# OneWireGateway_2x_0_1.net
KiCad netlist of a schematic drawn in EAGLE
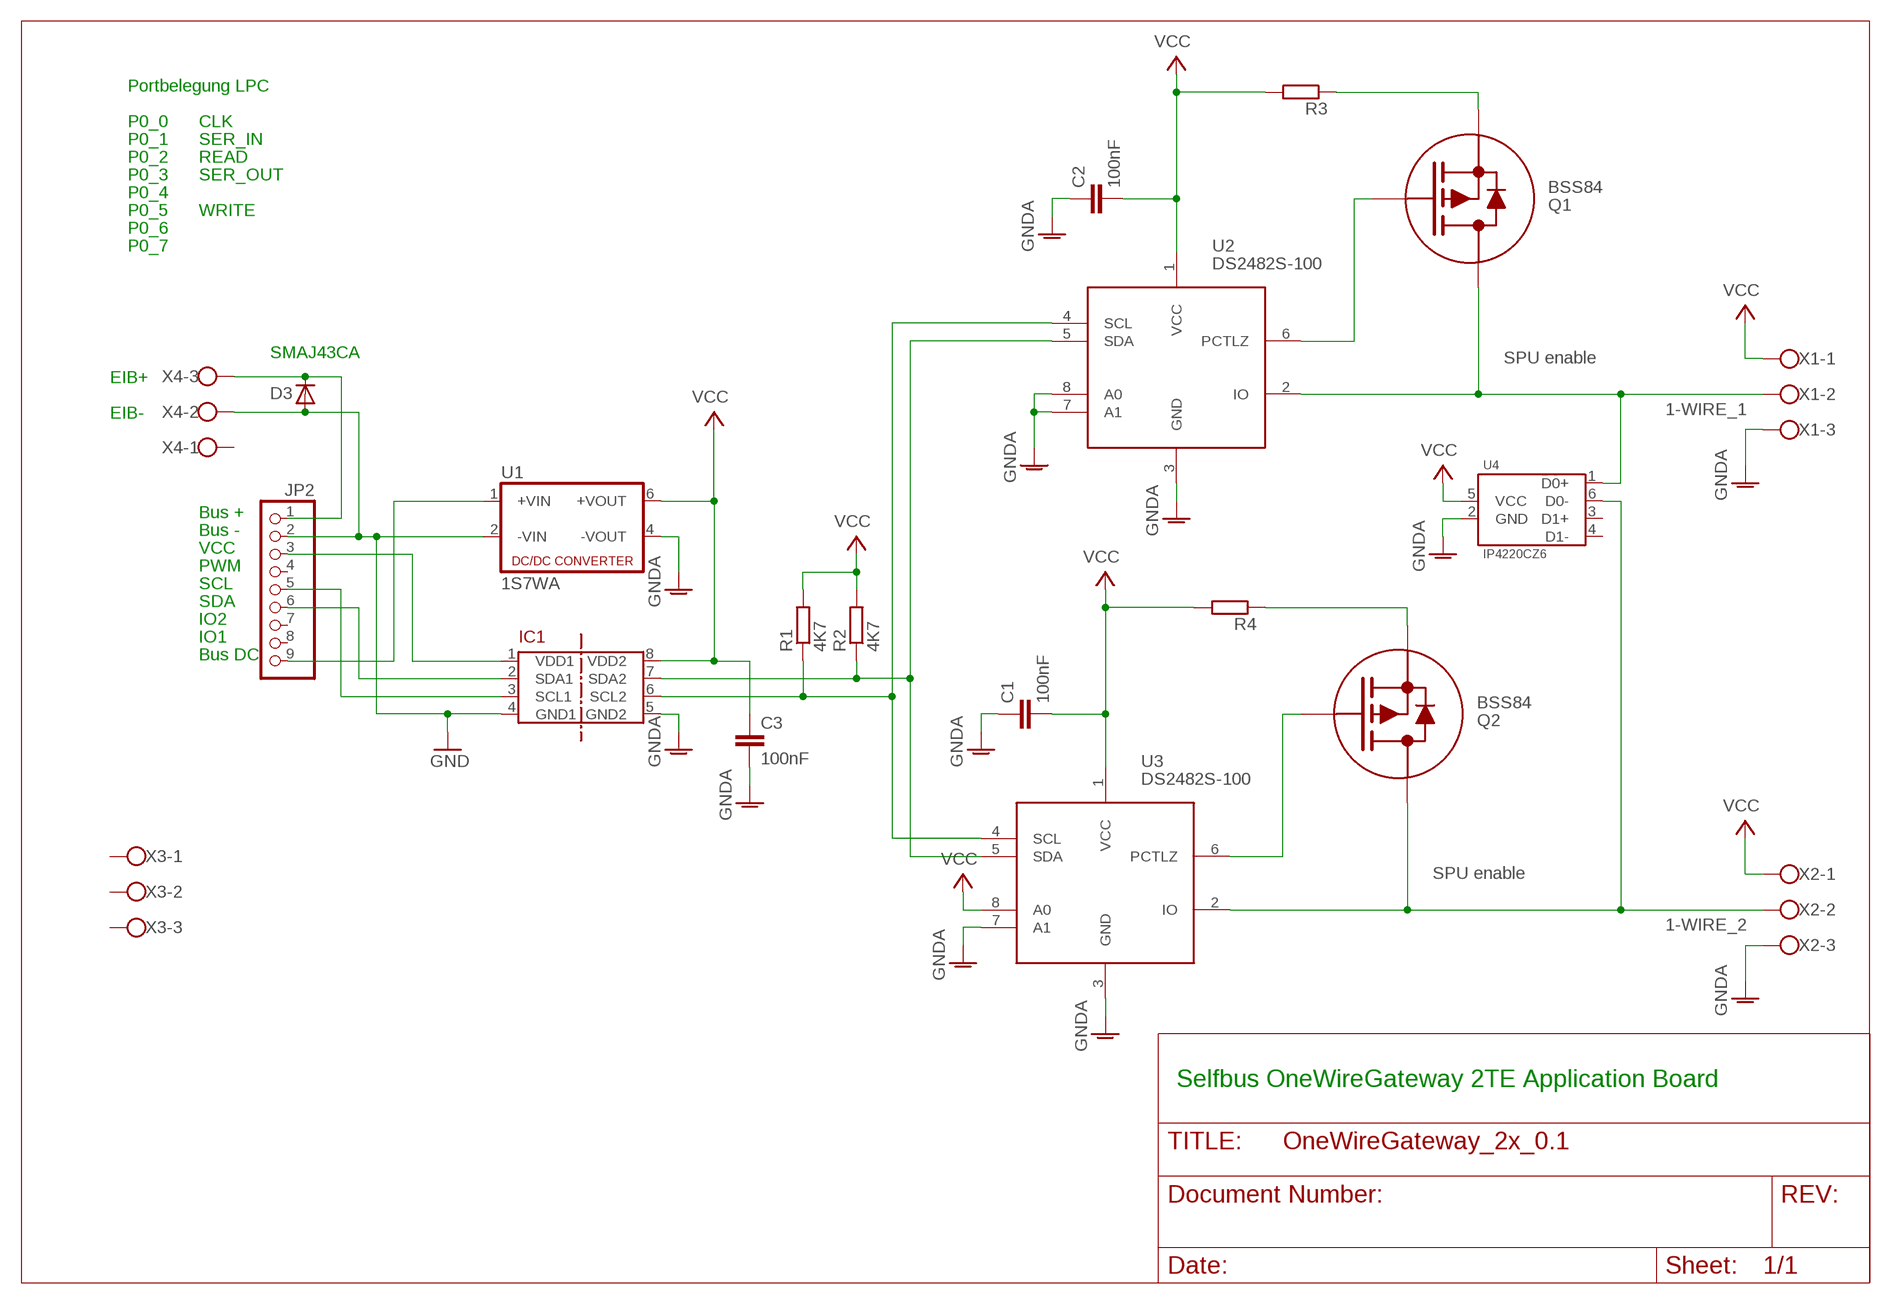
[diagram p0: schematic, sheet 1]

(export (version "E")
  (design (tool "Eeschema 10.0.6"))
  (components
    (comp (ref "C1")
      (value "100nF")
      (footprint "eagle-import:C0805")
      (libsource (lib "eagle-import") (part "C-EUC0805"))
    )
    (comp (ref "C2")
      (value "100nF")
      (footprint "eagle-import:C0805")
      (libsource (lib "eagle-import") (part "C-EUC0805"))
    )
    (comp (ref "C3")
      (value "100nF")
      (footprint "eagle-import:C0805")
      (libsource (lib "eagle-import") (part "C-EUC0805"))
    )
    (comp (ref "D3")
      (value "D-SMB")
      (footprint "eagle-import:SMB")
      (libsource (lib "eagle-import") (part "D-SMB"))
    )
    (comp (ref "IC1")
      (value "ADUM1250")
      (footprint "eagle-import:SO08")
      (libsource (lib "eagle-import") (part "ADUM1250"))
    )
    (comp (ref "JP2")
      (value "PINHD-1X9")
      (footprint "eagle-import:1X09")
      (libsource (lib "eagle-import") (part "PINHD-1X9"))
    )
    (comp (ref "Q1")
      (value "BSS84")
      (footprint "eagle-import:SOT-23-3")
      (fields (field (name "MF") "Fairchild Semiconductor"))
      (libsource (lib "eagle-import") (part "BSS841"))
    )
    (comp (ref "Q2")
      (value "BSS84")
      (footprint "eagle-import:SOT-23-3")
      (fields (field (name "MF") "Fairchild Semiconductor"))
      (libsource (lib "eagle-import") (part "BSS841"))
    )
    (comp (ref "R1")
      (value "4K7")
      (footprint "eagle-import:R0805")
      (libsource (lib "eagle-import") (part "R-EU_R0805"))
    )
    (comp (ref "R2")
      (value "4K7")
      (footprint "eagle-import:R0805")
      (libsource (lib "eagle-import") (part "R-EU_R0805"))
    )
    (comp (ref "R3")
      (value "R-EU_R0805")
      (footprint "eagle-import:R0805")
      (libsource (lib "eagle-import") (part "R-EU_R0805"))
    )
    (comp (ref "R4")
      (value "R-EU_R0805")
      (footprint "eagle-import:R0805")
      (libsource (lib "eagle-import") (part "R-EU_R0805"))
    )
    (comp (ref "U1")
      (value "1S7WA")
      (footprint "eagle-import:7PIN_SIP")
      (libsource (lib "eagle-import") (part "1S7WA"))
    )
    (comp (ref "U2")
      (value "DS2482S-100")
      (footprint "eagle-import:SO8")
      (fields (field (name "MF") "Maxim Integrated") (field (name "MPN") "DS2482-100+"))
      (libsource (lib "eagle-import") (part "DS2482-100+1"))
    )
    (comp (ref "U3")
      (value "DS2482S-100")
      (footprint "eagle-import:SO8")
      (fields (field (name "MF") "Maxim Integrated") (field (name "MPN") "DS2482-100+"))
      (libsource (lib "eagle-import") (part "DS2482-100+1"))
    )
    (comp (ref "U4")
      (value "IP4220CZ6")
      (footprint "eagle-import:SOT-6")
      (libsource (lib "eagle-import") (part "IP4220CZ6"))
    )
    (comp (ref "X1")
      (value "W237-03P")
      (footprint "eagle-import:W237-133")
      (libsource (lib "eagle-import") (part "W237-03P"))
    )
    (comp (ref "X2")
      (value "W237-03P")
      (footprint "eagle-import:W237-133")
      (libsource (lib "eagle-import") (part "W237-03P"))
    )
    (comp (ref "X3")
      (value "W237-3E")
      (footprint "eagle-import:W237-3E")
      (libsource (lib "eagle-import") (part "W237-3E"))
    )
    (comp (ref "X4")
      (value "W237-3E")
      (footprint "eagle-import:W237-3E")
      (libsource (lib "eagle-import") (part "W237-3E"))
    )
  )
  (nets
    (net (code "1") (name "/1-WIRE_1") (class "Default")
      (node (ref "Q1") (pin "3") (pinfunction "D_3") (pintype "bidirectional"))
      (node (ref "U2") (pin "2") (pinfunction "IO_2") (pintype "bidirectional"))
      (node (ref "U4") (pin "1") (pinfunction "D0+_1") (pintype "bidirectional"))
      (node (ref "X1") (pin "2") (pinfunction "KL_2") (pintype "passive"))
    )
    (net (code "2") (name "/1-WIRE_2") (class "Default")
      (node (ref "Q2") (pin "3") (pinfunction "D_3") (pintype "bidirectional"))
      (node (ref "U3") (pin "2") (pinfunction "IO_2") (pintype "bidirectional"))
      (node (ref "U4") (pin "6") (pinfunction "D0-_6") (pintype "bidirectional"))
      (node (ref "X2") (pin "2") (pinfunction "KL_2") (pintype "passive"))
    )
    (net (code "3") (name "GND") (class "Default")
      (node (ref "D3") (pin "2") (pinfunction "A_2") (pintype "passive"))
      (node (ref "IC1") (pin "4") (pinfunction "GND1_4") (pintype "power_in"))
      (node (ref "JP2") (pin "2") (pinfunction "2_2") (pintype "passive"))
      (node (ref "U1") (pin "2") (pinfunction "-VIN_2") (pintype "passive"))
      (node (ref "X4") (pin "2") (pinfunction "KL_2") (pintype "passive"))
    )
    (net (code "4") (name "GNDA") (class "Default")
      (node (ref "C1") (pin "1") (pinfunction "1_1") (pintype "passive"))
      (node (ref "C2") (pin "1") (pinfunction "1_1") (pintype "passive"))
      (node (ref "C3") (pin "2") (pinfunction "2_2") (pintype "passive"))
      (node (ref "IC1") (pin "5") (pinfunction "GND2_5") (pintype "power_in"))
      (node (ref "U1") (pin "4") (pinfunction "-VOUT_4") (pintype "passive"))
      (node (ref "U2") (pin "3") (pinfunction "GND_3") (pintype "bidirectional"))
      (node (ref "U2") (pin "7") (pinfunction "A1_7") (pintype "bidirectional"))
      (node (ref "U2") (pin "8") (pinfunction "A0_8") (pintype "bidirectional"))
      (node (ref "U3") (pin "3") (pinfunction "GND_3") (pintype "bidirectional"))
      (node (ref "U3") (pin "7") (pinfunction "A1_7") (pintype "bidirectional"))
      (node (ref "U4") (pin "2") (pinfunction "GND_2") (pintype "bidirectional"))
      (node (ref "X1") (pin "3") (pinfunction "KL_3") (pintype "passive"))
      (node (ref "X2") (pin "3") (pinfunction "KL_3") (pintype "passive"))
    )
    (net (code "5") (name "Net-(D3-C)") (class "Default")
      (node (ref "D3") (pin "1") (pinfunction "C_1") (pintype "passive"))
      (node (ref "JP2") (pin "1") (pinfunction "1_1") (pintype "passive"))
      (node (ref "X4") (pin "3") (pinfunction "KL_3") (pintype "passive"))
    )
    (net (code "6") (name "Net-(IC1-SCL1)") (class "Default")
      (node (ref "IC1") (pin "3") (pinfunction "SCL1_3") (pintype "bidirectional"))
      (node (ref "JP2") (pin "5") (pinfunction "5_5") (pintype "passive"))
    )
    (net (code "7") (name "Net-(IC1-SCL2)") (class "Default")
      (node (ref "IC1") (pin "6") (pinfunction "SCL2_6") (pintype "bidirectional"))
      (node (ref "R1") (pin "1") (pinfunction "1_1") (pintype "passive"))
      (node (ref "U2") (pin "4") (pinfunction "SCL_4") (pintype "bidirectional"))
      (node (ref "U3") (pin "4") (pinfunction "SCL_4") (pintype "bidirectional"))
    )
    (net (code "8") (name "Net-(IC1-SDA1)") (class "Default")
      (node (ref "IC1") (pin "2") (pinfunction "SDA1_2") (pintype "bidirectional"))
      (node (ref "JP2") (pin "6") (pinfunction "6_6") (pintype "passive"))
    )
    (net (code "9") (name "Net-(IC1-SDA2)") (class "Default")
      (node (ref "IC1") (pin "7") (pinfunction "SDA2_7") (pintype "bidirectional"))
      (node (ref "R2") (pin "1") (pinfunction "1_1") (pintype "passive"))
      (node (ref "U2") (pin "5") (pinfunction "SDA_5") (pintype "bidirectional"))
      (node (ref "U3") (pin "5") (pinfunction "SDA_5") (pintype "bidirectional"))
    )
    (net (code "10") (name "Net-(IC1-VDD1)") (class "Default")
      (node (ref "IC1") (pin "1") (pinfunction "VDD1_1") (pintype "power_in"))
      (node (ref "JP2") (pin "3") (pinfunction "3_3") (pintype "passive"))
    )
    (net (code "11") (name "Net-(Q1-G)") (class "Default")
      (node (ref "Q1") (pin "1") (pinfunction "G_1") (pintype "bidirectional"))
      (node (ref "U2") (pin "6") (pinfunction "PCTLZ_6") (pintype "bidirectional"))
    )
    (net (code "12") (name "Net-(Q1-S)") (class "Default")
      (node (ref "Q1") (pin "2") (pinfunction "S_2") (pintype "bidirectional"))
      (node (ref "R3") (pin "1") (pinfunction "1_1") (pintype "passive"))
    )
    (net (code "13") (name "Net-(Q2-G)") (class "Default")
      (node (ref "Q2") (pin "1") (pinfunction "G_1") (pintype "bidirectional"))
      (node (ref "U3") (pin "6") (pinfunction "PCTLZ_6") (pintype "bidirectional"))
    )
    (net (code "14") (name "Net-(Q2-S)") (class "Default")
      (node (ref "Q2") (pin "2") (pinfunction "S_2") (pintype "bidirectional"))
      (node (ref "R4") (pin "1") (pinfunction "1_1") (pintype "passive"))
    )
    (net (code "15") (name "Net-(U1-+VIN)") (class "Default")
      (node (ref "JP2") (pin "9") (pinfunction "9_9") (pintype "passive"))
      (node (ref "U1") (pin "1") (pinfunction "+VIN_1") (pintype "passive"))
    )
    (net (code "16") (name "VCC") (class "Default")
      (node (ref "C1") (pin "2") (pinfunction "2_2") (pintype "passive"))
      (node (ref "C2") (pin "2") (pinfunction "2_2") (pintype "passive"))
      (node (ref "C3") (pin "1") (pinfunction "1_1") (pintype "passive"))
      (node (ref "IC1") (pin "8") (pinfunction "VDD2_8") (pintype "power_in"))
      (node (ref "R1") (pin "2") (pinfunction "2_2") (pintype "passive"))
      (node (ref "R2") (pin "2") (pinfunction "2_2") (pintype "passive"))
      (node (ref "R3") (pin "2") (pinfunction "2_2") (pintype "passive"))
      (node (ref "R4") (pin "2") (pinfunction "2_2") (pintype "passive"))
      (node (ref "U1") (pin "6") (pinfunction "+VOUT_6") (pintype "passive"))
      (node (ref "U2") (pin "1") (pinfunction "VCC_1") (pintype "bidirectional"))
      (node (ref "U3") (pin "1") (pinfunction "VCC_1") (pintype "bidirectional"))
      (node (ref "U3") (pin "8") (pinfunction "A0_8") (pintype "bidirectional"))
      (node (ref "U4") (pin "5") (pinfunction "VCC_5") (pintype "bidirectional"))
      (node (ref "X1") (pin "1") (pinfunction "KL_1") (pintype "passive"))
      (node (ref "X2") (pin "1") (pinfunction "KL_1") (pintype "passive"))
    )
    (net (code "17") (name "unconnected-(JP2-Pad4)") (class "Default")
      (node (ref "JP2") (pin "4") (pinfunction "4_4") (pintype "passive"))
    )
    (net (code "18") (name "unconnected-(JP2-Pad7)") (class "Default")
      (node (ref "JP2") (pin "7") (pinfunction "7_7") (pintype "passive"))
    )
    (net (code "19") (name "unconnected-(JP2-Pad8)") (class "Default")
      (node (ref "JP2") (pin "8") (pinfunction "8_8") (pintype "passive"))
    )
    (net (code "20") (name "unconnected-(U4-D1+-Pad3)") (class "Default")
      (node (ref "U4") (pin "3") (pinfunction "D1+_3") (pintype "bidirectional"))
    )
    (net (code "21") (name "unconnected-(U4-D1--Pad4)") (class "Default")
      (node (ref "U4") (pin "4") (pinfunction "D1-_4") (pintype "bidirectional"))
    )
    (net (code "22") (name "unconnected-(X3A-KL-Pad1)") (class "Default")
      (node (ref "X3") (pin "1") (pinfunction "KL_1") (pintype "passive"))
    )
    (net (code "23") (name "unconnected-(X3B-KL-Pad2)") (class "Default")
      (node (ref "X3") (pin "2") (pinfunction "KL_2") (pintype "passive"))
    )
    (net (code "24") (name "unconnected-(X3C-KL-Pad3)") (class "Default")
      (node (ref "X3") (pin "3") (pinfunction "KL_3") (pintype "passive"))
    )
    (net (code "25") (name "unconnected-(X4A-KL-Pad1)") (class "Default")
      (node (ref "X4") (pin "1") (pinfunction "KL_1") (pintype "passive"))
    )
  )
)
